# 06_EXT_UART.net
KiCad netlist of a schematic drawn in Altium Designer
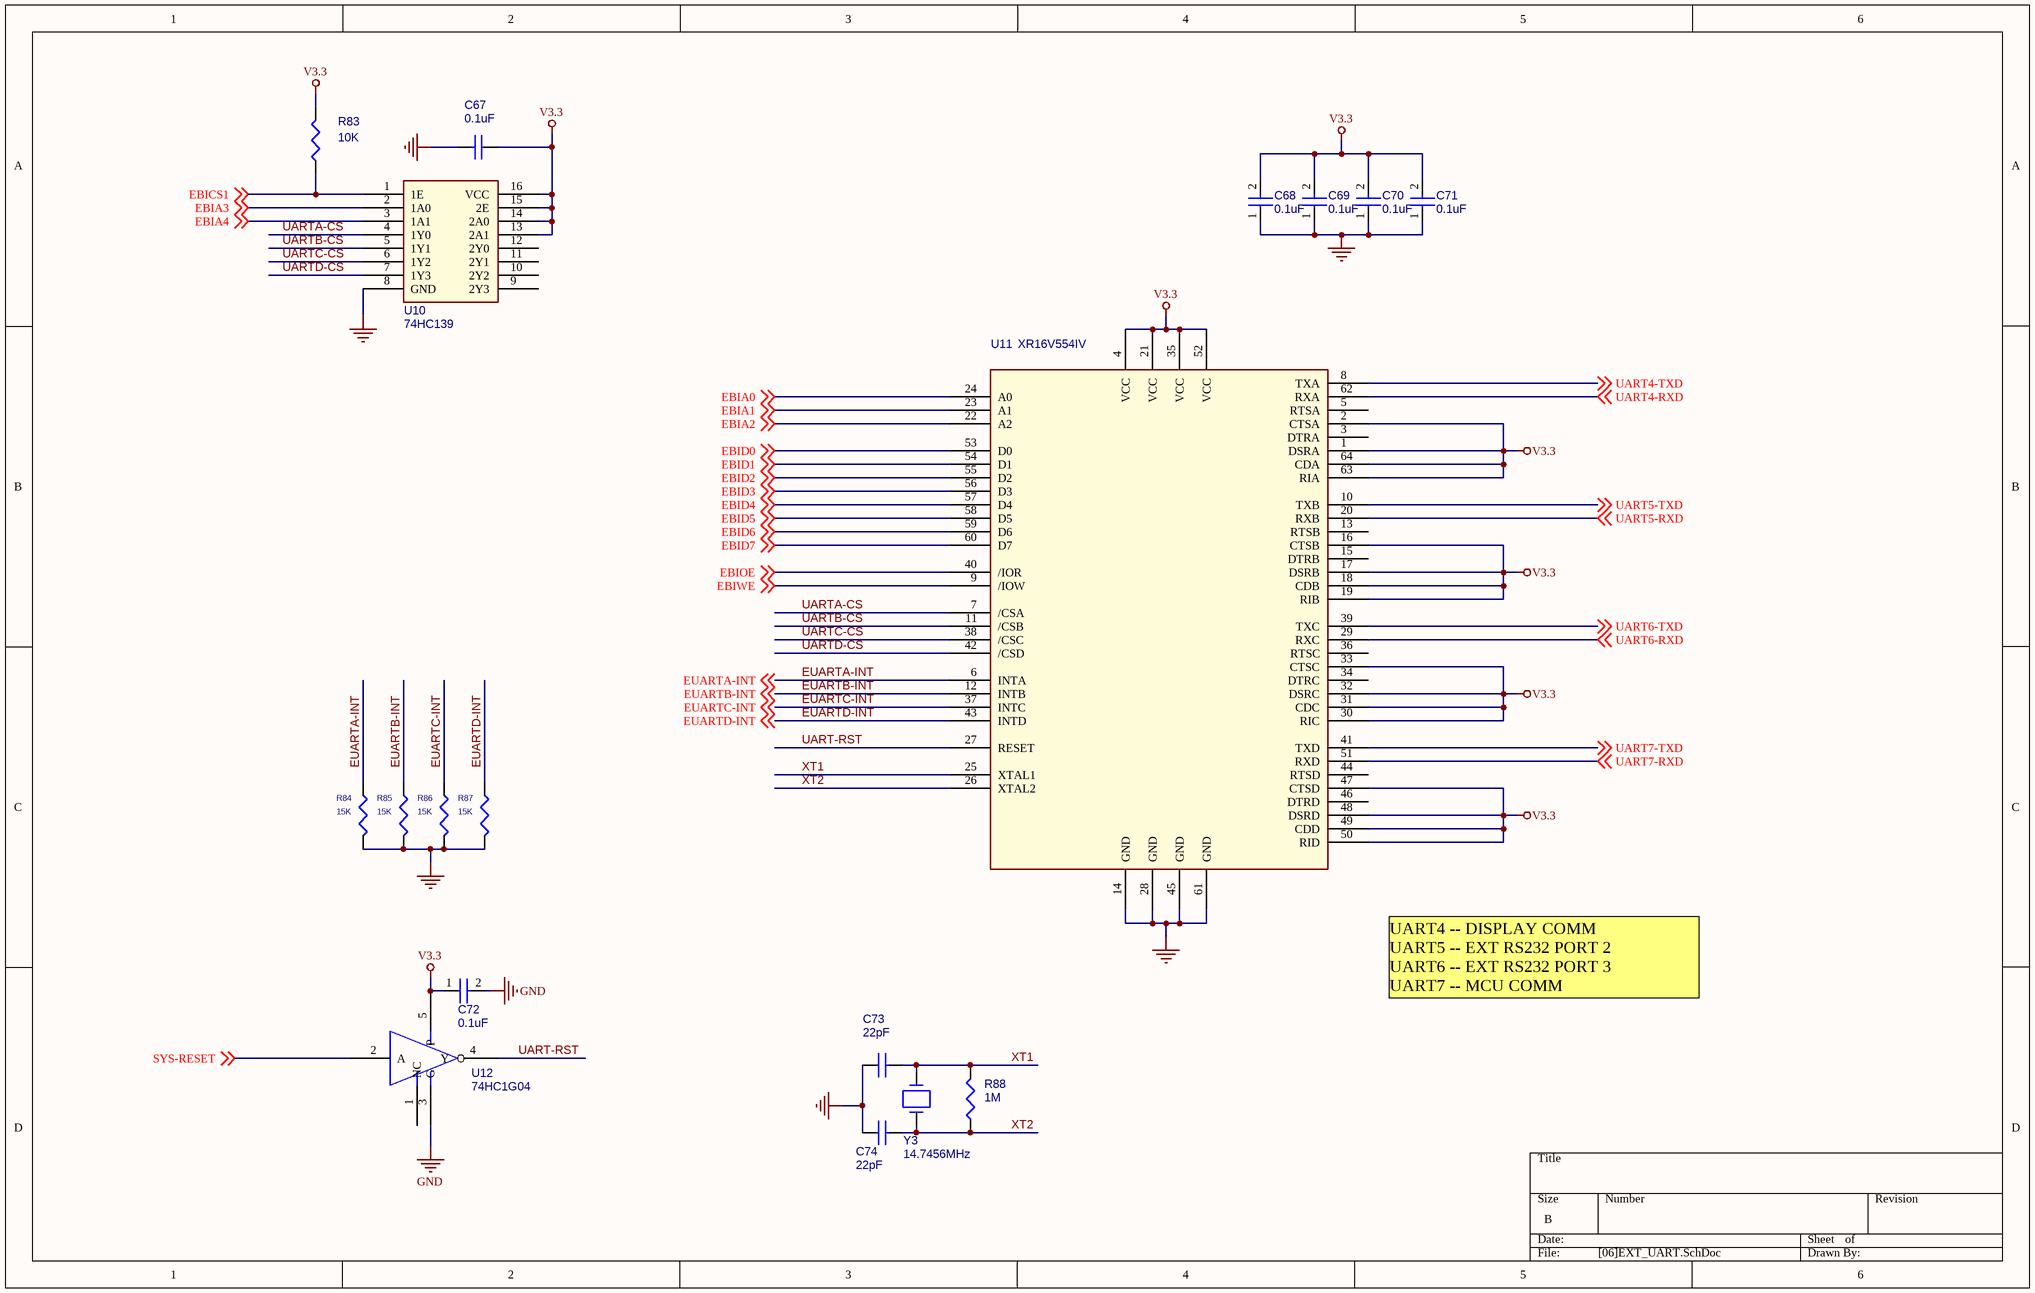
[diagram p0: [06]EXT_UART.SchDoc]

(export (version "E")
  (design (tool "Eeschema 10.0.6"))
  (components
    (comp (ref "C67") (value "0.1uF") (libsource (lib "") (part "CAP NP_Dup2_1")))
    (comp (ref "C68") (value "0.1uF") (libsource (lib "*") (part "CAP NP_Dup2")))
    (comp (ref "C69") (value "0.1uF") (libsource (lib "*") (part "CAP NP_Dup2")))
    (comp (ref "C70") (value "0.1uF") (libsource (lib "*") (part "CAP NP_Dup2")))
    (comp (ref "C71") (value "0.1uF") (libsource (lib "*") (part "CAP NP_Dup2")))
    (comp (ref "C72") (value "0.1uF") (footprint "0603") (libsource (lib "*") (part "CAP NP_Dup2")))
    (comp (ref "C73") (value "22pF") (libsource (lib "*") (part "CAP_Dup1")))
    (comp (ref "C74") (value "22pF") (libsource (lib "*") (part "CAP_Dup1")))
    (comp (ref "R83") (value "10K") (libsource (lib "*") (part "R_Dup1")))
    (comp (ref "R84") (value "15K") (libsource (lib "*") (part "R_Dup1")))
    (comp (ref "R85") (value "15K") (libsource (lib "*") (part "R_Dup1")))
    (comp (ref "R86") (value "15K") (libsource (lib "*") (part "R_Dup1")))
    (comp (ref "R87") (value "15K") (libsource (lib "*") (part "R_Dup1")))
    (comp (ref "R88") (value "1M") (libsource (lib "*") (part "RESISTOR")))
    (comp (ref "U10") (value "74HC139") (libsource (lib "*") (part "74HC139")))
    (comp (ref "U11") (value "XR16V554IV") (libsource (lib "*") (part "XR16V554IV_4")))
    (comp (ref "U12") (value "74HC1G04") (libsource (lib "*") (part "74LVC1G04GW_SOT353-5")))
    (comp (ref "Y3") (value "14.7456MHz") (libsource (lib "*") (part "CRYSTAL")))
  )
  (nets
    (net (code "1") (name "/UART-RST") (class "Default")
      (node (ref "U11") (pin "27") (pinfunction "RESET_27") (pintype "passive"))
      (node (ref "U12") (pin "4") (pinfunction "Y_4") (pintype "passive"))
    )
    (net (code "2") (name "/UARTA-CS") (class "Default")
      (node (ref "U10") (pin "4") (pinfunction "1Y0_4") (pintype "passive"))
      (node (ref "U11") (pin "7") (pinfunction "/CSA_7") (pintype "passive"))
    )
    (net (code "3") (name "/UARTB-CS") (class "Default")
      (node (ref "U10") (pin "5") (pinfunction "1Y1_5") (pintype "passive"))
      (node (ref "U11") (pin "11") (pinfunction "/CSB_11") (pintype "passive"))
    )
    (net (code "4") (name "/UARTC-CS") (class "Default")
      (node (ref "U10") (pin "6") (pinfunction "1Y2_6") (pintype "passive"))
      (node (ref "U11") (pin "38") (pinfunction "/CSC_38") (pintype "passive"))
    )
    (net (code "5") (name "/UARTD-CS") (class "Default")
      (node (ref "U10") (pin "7") (pinfunction "1Y3_7") (pintype "passive"))
      (node (ref "U11") (pin "42") (pinfunction "/CSD_42") (pintype "passive"))
    )
    (net (code "6") (name "/XT1") (class "Default")
      (node (ref "C73") (pin "2") (pinfunction "2_2") (pintype "passive"))
      (node (ref "R88") (pin "2") (pinfunction "2_2") (pintype "passive"))
      (node (ref "U11") (pin "25") (pinfunction "XTAL1_25") (pintype "passive"))
      (node (ref "Y3") (pin "2") (pinfunction "2_2") (pintype "passive"))
    )
    (net (code "7") (name "/XT2") (class "Default")
      (node (ref "C74") (pin "2") (pinfunction "2_2") (pintype "passive"))
      (node (ref "R88") (pin "1") (pinfunction "1_1") (pintype "passive"))
      (node (ref "U11") (pin "26") (pinfunction "XTAL2_26") (pintype "passive"))
      (node (ref "Y3") (pin "1") (pinfunction "1_1") (pintype "passive"))
    )
    (net (code "8") (name "EBIA0") (class "Default")
      (node (ref "U11") (pin "24") (pinfunction "A0_24") (pintype "passive"))
    )
    (net (code "9") (name "EBIA1") (class "Default")
      (node (ref "U11") (pin "23") (pinfunction "A1_23") (pintype "passive"))
    )
    (net (code "10") (name "EBIA2") (class "Default")
      (node (ref "U11") (pin "22") (pinfunction "A2_22") (pintype "passive"))
    )
    (net (code "11") (name "EBIA3") (class "Default")
      (node (ref "U10") (pin "2") (pinfunction "1A0_2") (pintype "passive"))
    )
    (net (code "12") (name "EBIA4") (class "Default")
      (node (ref "U10") (pin "3") (pinfunction "1A1_3") (pintype "passive"))
    )
    (net (code "13") (name "EBICS1") (class "Default")
      (node (ref "R83") (pin "1") (pinfunction "1_1") (pintype "passive"))
      (node (ref "U10") (pin "1") (pinfunction "1E_1") (pintype "passive"))
    )
    (net (code "14") (name "EBID0") (class "Default")
      (node (ref "U11") (pin "53") (pinfunction "D0_53") (pintype "passive"))
    )
    (net (code "15") (name "EBID1") (class "Default")
      (node (ref "U11") (pin "54") (pinfunction "D1_54") (pintype "passive"))
    )
    (net (code "16") (name "EBID2") (class "Default")
      (node (ref "U11") (pin "55") (pinfunction "D2_55") (pintype "passive"))
    )
    (net (code "17") (name "EBID3") (class "Default")
      (node (ref "U11") (pin "56") (pinfunction "D3_56") (pintype "passive"))
    )
    (net (code "18") (name "EBID4") (class "Default")
      (node (ref "U11") (pin "57") (pinfunction "D4_57") (pintype "passive"))
    )
    (net (code "19") (name "EBID5") (class "Default")
      (node (ref "U11") (pin "58") (pinfunction "D5_58") (pintype "passive"))
    )
    (net (code "20") (name "EBID6") (class "Default")
      (node (ref "U11") (pin "59") (pinfunction "D6_59") (pintype "passive"))
    )
    (net (code "21") (name "EBID7") (class "Default")
      (node (ref "U11") (pin "60") (pinfunction "D7_60") (pintype "passive"))
    )
    (net (code "22") (name "EBIOE") (class "Default")
      (node (ref "U11") (pin "40") (pinfunction "/IOR_40") (pintype "passive"))
    )
    (net (code "23") (name "EBIWE") (class "Default")
      (node (ref "U11") (pin "9") (pinfunction "/IOW_9") (pintype "passive"))
    )
    (net (code "24") (name "EUARTA-INT") (class "Default")
      (node (ref "R84") (pin "1") (pinfunction "1_1") (pintype "passive"))
      (node (ref "U11") (pin "6") (pinfunction "INTA_6") (pintype "passive"))
    )
    (net (code "25") (name "EUARTB-INT") (class "Default")
      (node (ref "R85") (pin "1") (pinfunction "1_1") (pintype "passive"))
      (node (ref "U11") (pin "12") (pinfunction "INTB_12") (pintype "passive"))
    )
    (net (code "26") (name "EUARTC-INT") (class "Default")
      (node (ref "R86") (pin "1") (pinfunction "1_1") (pintype "passive"))
      (node (ref "U11") (pin "37") (pinfunction "INTC_37") (pintype "passive"))
    )
    (net (code "27") (name "EUARTD-INT") (class "Default")
      (node (ref "R87") (pin "1") (pinfunction "1_1") (pintype "passive"))
      (node (ref "U11") (pin "43") (pinfunction "INTD_43") (pintype "passive"))
    )
    (net (code "28") (name "GND") (class "Default")
      (node (ref "C67") (pin "2") (pinfunction "2_2") (pintype "passive"))
      (node (ref "C68") (pin "1") (pinfunction "1_1") (pintype "passive"))
      (node (ref "C69") (pin "1") (pinfunction "1_1") (pintype "passive"))
      (node (ref "C70") (pin "1") (pinfunction "1_1") (pintype "passive"))
      (node (ref "C71") (pin "1") (pinfunction "1_1") (pintype "passive"))
      (node (ref "C72") (pin "2") (pinfunction "2_2") (pintype "passive"))
      (node (ref "C73") (pin "1") (pinfunction "1_1") (pintype "passive"))
      (node (ref "C74") (pin "1") (pinfunction "1_1") (pintype "passive"))
      (node (ref "R84") (pin "2") (pinfunction "2_2") (pintype "passive"))
      (node (ref "R85") (pin "2") (pinfunction "2_2") (pintype "passive"))
      (node (ref "R86") (pin "2") (pinfunction "2_2") (pintype "passive"))
      (node (ref "R87") (pin "2") (pinfunction "2_2") (pintype "passive"))
      (node (ref "U10") (pin "8") (pinfunction "GND_8") (pintype "passive"))
      (node (ref "U11") (pin "14") (pinfunction "GND_14") (pintype "power_in"))
      (node (ref "U11") (pin "28") (pinfunction "GND_28") (pintype "power_in"))
      (node (ref "U11") (pin "45") (pinfunction "GND_45") (pintype "power_in"))
      (node (ref "U11") (pin "61") (pinfunction "GND_61") (pintype "power_in"))
      (node (ref "U12") (pin "3") (pinfunction "G_3") (pintype "passive"))
    )
    (net (code "29") (name "SYS-RESET") (class "Default")
      (node (ref "U12") (pin "2") (pinfunction "A_2") (pintype "passive"))
    )
    (net (code "30") (name "UART4-RXD") (class "Default")
      (node (ref "U11") (pin "62") (pinfunction "RXA_62") (pintype "passive"))
    )
    (net (code "31") (name "UART4-TXD") (class "Default")
      (node (ref "U11") (pin "8") (pinfunction "TXA_8") (pintype "passive"))
    )
    (net (code "32") (name "UART5-RXD") (class "Default")
      (node (ref "U11") (pin "20") (pinfunction "RXB_20") (pintype "passive"))
    )
    (net (code "33") (name "UART5-TXD") (class "Default")
      (node (ref "U11") (pin "10") (pinfunction "TXB_10") (pintype "passive"))
    )
    (net (code "34") (name "UART6-RXD") (class "Default")
      (node (ref "U11") (pin "29") (pinfunction "RXC_29") (pintype "passive"))
    )
    (net (code "35") (name "UART6-TXD") (class "Default")
      (node (ref "U11") (pin "39") (pinfunction "TXC_39") (pintype "passive"))
    )
    (net (code "36") (name "UART7-RXD") (class "Default")
      (node (ref "U11") (pin "51") (pinfunction "RXD_51") (pintype "passive"))
    )
    (net (code "37") (name "UART7-TXD") (class "Default")
      (node (ref "U11") (pin "41") (pinfunction "TXD_41") (pintype "passive"))
    )
    (net (code "38") (name "V3.3") (class "Default")
      (node (ref "C67") (pin "1") (pinfunction "1_1") (pintype "passive"))
      (node (ref "C68") (pin "2") (pinfunction "2_2") (pintype "passive"))
      (node (ref "C69") (pin "2") (pinfunction "2_2") (pintype "passive"))
      (node (ref "C70") (pin "2") (pinfunction "2_2") (pintype "passive"))
      (node (ref "C71") (pin "2") (pinfunction "2_2") (pintype "passive"))
      (node (ref "C72") (pin "1") (pinfunction "1_1") (pintype "passive"))
      (node (ref "R83") (pin "2") (pinfunction "2_2") (pintype "passive"))
      (node (ref "U10") (pin "13") (pinfunction "2A1_13") (pintype "passive"))
      (node (ref "U10") (pin "14") (pinfunction "2A0_14") (pintype "passive"))
      (node (ref "U10") (pin "15") (pinfunction "2E_15") (pintype "passive"))
      (node (ref "U10") (pin "16") (pinfunction "VCC_16") (pintype "passive"))
      (node (ref "U11") (pin "1") (pinfunction "DSRA_1") (pintype "passive"))
      (node (ref "U11") (pin "16") (pinfunction "CTSB_16") (pintype "passive"))
      (node (ref "U11") (pin "17") (pinfunction "DSRB_17") (pintype "passive"))
      (node (ref "U11") (pin "18") (pinfunction "CDB_18") (pintype "passive"))
      (node (ref "U11") (pin "19") (pinfunction "RIB_19") (pintype "passive"))
      (node (ref "U11") (pin "2") (pinfunction "CTSA_2") (pintype "passive"))
      (node (ref "U11") (pin "21") (pinfunction "VCC_21") (pintype "power_in"))
      (node (ref "U11") (pin "30") (pinfunction "RIC_30") (pintype "passive"))
      (node (ref "U11") (pin "31") (pinfunction "CDC_31") (pintype "passive"))
      (node (ref "U11") (pin "32") (pinfunction "DSRC_32") (pintype "passive"))
      (node (ref "U11") (pin "33") (pinfunction "CTSC_33") (pintype "passive"))
      (node (ref "U11") (pin "35") (pinfunction "VCC_35") (pintype "power_in"))
      (node (ref "U11") (pin "4") (pinfunction "VCC_4") (pintype "power_in"))
      (node (ref "U11") (pin "47") (pinfunction "CTSD_47") (pintype "passive"))
      (node (ref "U11") (pin "48") (pinfunction "DSRD_48") (pintype "passive"))
      (node (ref "U11") (pin "49") (pinfunction "CDD_49") (pintype "passive"))
      (node (ref "U11") (pin "50") (pinfunction "RID_50") (pintype "passive"))
      (node (ref "U11") (pin "52") (pinfunction "VCC_52") (pintype "power_in"))
      (node (ref "U11") (pin "63") (pinfunction "RIA_63") (pintype "passive"))
      (node (ref "U11") (pin "64") (pinfunction "CDA_64") (pintype "passive"))
      (node (ref "U12") (pin "5") (pinfunction "P_5") (pintype "passive"))
    )
    (net (code "39") (name "unconnected-(U10-2Y0-Pad12)") (class "Default")
      (node (ref "U10") (pin "12") (pinfunction "2Y0_12") (pintype "passive"))
    )
    (net (code "40") (name "unconnected-(U10-2Y1-Pad11)") (class "Default")
      (node (ref "U10") (pin "11") (pinfunction "2Y1_11") (pintype "passive"))
    )
    (net (code "41") (name "unconnected-(U10-2Y2-Pad10)") (class "Default")
      (node (ref "U10") (pin "10") (pinfunction "2Y2_10") (pintype "passive"))
    )
    (net (code "42") (name "unconnected-(U10-2Y3-Pad9)") (class "Default")
      (node (ref "U10") (pin "9") (pinfunction "2Y3_9") (pintype "passive"))
    )
    (net (code "43") (name "unconnected-(U11-DTRA-Pad3)") (class "Default")
      (node (ref "U11") (pin "3") (pinfunction "DTRA_3") (pintype "passive"))
    )
    (net (code "44") (name "unconnected-(U11-DTRB-Pad15)") (class "Default")
      (node (ref "U11") (pin "15") (pinfunction "DTRB_15") (pintype "passive"))
    )
    (net (code "45") (name "unconnected-(U11-DTRC-Pad34)") (class "Default")
      (node (ref "U11") (pin "34") (pinfunction "DTRC_34") (pintype "passive"))
    )
    (net (code "46") (name "unconnected-(U11-DTRD-Pad46)") (class "Default")
      (node (ref "U11") (pin "46") (pinfunction "DTRD_46") (pintype "passive"))
    )
    (net (code "47") (name "unconnected-(U11-RTSA-Pad5)") (class "Default")
      (node (ref "U11") (pin "5") (pinfunction "RTSA_5") (pintype "passive"))
    )
    (net (code "48") (name "unconnected-(U11-RTSB-Pad13)") (class "Default")
      (node (ref "U11") (pin "13") (pinfunction "RTSB_13") (pintype "passive"))
    )
    (net (code "49") (name "unconnected-(U11-RTSC-Pad36)") (class "Default")
      (node (ref "U11") (pin "36") (pinfunction "RTSC_36") (pintype "passive"))
    )
    (net (code "50") (name "unconnected-(U11-RTSD-Pad44)") (class "Default")
      (node (ref "U11") (pin "44") (pinfunction "RTSD_44") (pintype "passive"))
    )
    (net (code "51") (name "unconnected-(U12-NC-Pad1)") (class "Default")
      (node (ref "U12") (pin "1") (pinfunction "NC_1") (pintype "passive"))
    )
  )
)
